# ina125.net
KiCad netlist of a schematic drawn in EAGLE
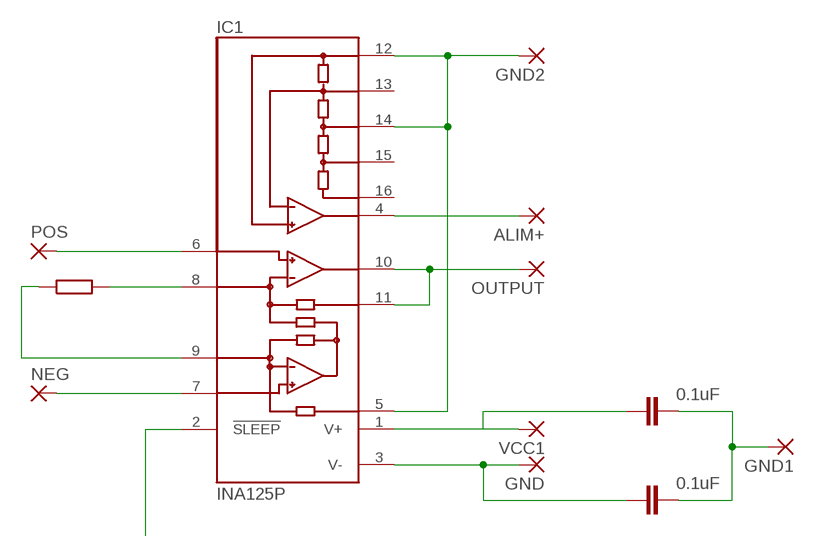
[diagram p0: schematic, sheet 1]

(export (version "E")
  (design (tool "Eeschema 10.0.6"))
  (components
    (comp (ref "ALIM+")
      (value "1,6/0,8")
      (footprint "eagle-import:1,6_0,8")
      (libsource (lib "eagle-import") (part "1,6/0,8"))
    )
    (comp (ref "C1")
      (value "0.1uF")
      (footprint "eagle-import:C2.5-3")
      (libsource (lib "eagle-import") (part "C2,5-3"))
    )
    (comp (ref "C2")
      (value "0.1uF")
      (footprint "eagle-import:C2.5-3")
      (libsource (lib "eagle-import") (part "C2,5-3"))
    )
    (comp (ref "GND")
      (value "1,6/0,8")
      (footprint "eagle-import:1,6_0,8")
      (libsource (lib "eagle-import") (part "1,6/0,8"))
    )
    (comp (ref "GND1")
      (value "1,6/0,8")
      (footprint "eagle-import:1,6_0,8")
      (libsource (lib "eagle-import") (part "1,6/0,8"))
    )
    (comp (ref "GND2")
      (value "1,6/0,8")
      (footprint "eagle-import:1,6_0,8")
      (libsource (lib "eagle-import") (part "1,6/0,8"))
    )
    (comp (ref "IC1")
      (value "INA125P")
      (footprint "eagle-import:DIL16")
      (libsource (lib "eagle-import") (part "INA125P"))
    )
    (comp (ref "NEG")
      (value "1,6/0,8")
      (footprint "eagle-import:1,6_0,8")
      (libsource (lib "eagle-import") (part "1,6/0,8"))
    )
    (comp (ref "OUTPUT")
      (value "1,6/0,8")
      (footprint "eagle-import:1,6_0,8")
      (libsource (lib "eagle-import") (part "1,6/0,8"))
    )
    (comp (ref "POS")
      (value "1,6/0,8")
      (footprint "eagle-import:1,6_0,8")
      (libsource (lib "eagle-import") (part "1,6/0,8"))
    )
    (comp (ref "VCC1")
      (value "1,6/0,8")
      (footprint "eagle-import:1,6_0,8")
      (libsource (lib "eagle-import") (part "1,6/0,8"))
    )
  )
  (nets
    (net (code "1") (name "Net-(ALIM+-P)") (class "Default")
      (node (ref "ALIM+") (pin "1") (pinfunction "P_1") (pintype "passive"))
      (node (ref "IC1") (pin "4") (pinfunction "REFOUT_4") (pintype "output"))
    )
    (net (code "2") (name "Net-(GND-P)") (class "Default")
      (node (ref "C2") (pin "1") (pinfunction "1_1") (pintype "passive"))
      (node (ref "GND") (pin "1") (pinfunction "P_1") (pintype "passive"))
      (node (ref "IC1") (pin "3") (pinfunction "V-_3") (pintype "power_in"))
    )
    (net (code "3") (name "Net-(GND1-P)") (class "Default")
      (node (ref "C1") (pin "2") (pinfunction "2_2") (pintype "passive"))
      (node (ref "C2") (pin "2") (pinfunction "2_2") (pintype "passive"))
      (node (ref "GND1") (pin "1") (pinfunction "P_1") (pintype "passive"))
    )
    (net (code "4") (name "Net-(GND2-P)") (class "Default")
      (node (ref "GND2") (pin "1") (pinfunction "P_1") (pintype "passive"))
      (node (ref "IC1") (pin "12") (pinfunction "REFCOM_12") (pintype "passive"))
      (node (ref "IC1") (pin "14") (pinfunction "REF2.5_14") (pintype "output"))
      (node (ref "IC1") (pin "5") (pinfunction "REF_5") (pintype "passive"))
    )
    (net (code "5") (name "Net-(IC1-+IN)") (class "Default")
      (node (ref "IC1") (pin "6") (pinfunction "+IN_6") (pintype "input"))
      (node (ref "POS") (pin "1") (pinfunction "P_1") (pintype "passive"))
    )
    (net (code "6") (name "Net-(IC1--IN)") (class "Default")
      (node (ref "IC1") (pin "7") (pinfunction "-IN_7") (pintype "input"))
      (node (ref "NEG") (pin "1") (pinfunction "P_1") (pintype "passive"))
    )
    (net (code "7") (name "Net-(IC1-OUT)") (class "Default")
      (node (ref "IC1") (pin "10") (pinfunction "OUT_10") (pintype "output"))
      (node (ref "IC1") (pin "11") (pinfunction "SENSE_11") (pintype "passive"))
      (node (ref "OUTPUT") (pin "1") (pinfunction "P_1") (pintype "passive"))
    )
    (net (code "8") (name "Net-(IC1-V+)") (class "Default")
      (node (ref "C1") (pin "1") (pinfunction "1_1") (pintype "passive"))
      (node (ref "IC1") (pin "1") (pinfunction "V+_1") (pintype "power_in"))
      (node (ref "VCC1") (pin "1") (pinfunction "P_1") (pintype "passive"))
    )
    (net (code "9") (name "unconnected-(IC1-REF5-Pad15)") (class "Default")
      (node (ref "IC1") (pin "15") (pinfunction "REF5_15") (pintype "output"))
    )
    (net (code "10") (name "unconnected-(IC1-REF10-Pad16)") (class "Default")
      (node (ref "IC1") (pin "16") (pinfunction "REF10_16") (pintype "output"))
    )
    (net (code "11") (name "unconnected-(IC1-REFBG-Pad13)") (class "Default")
      (node (ref "IC1") (pin "13") (pinfunction "REFBG_13") (pintype "output"))
    )
    (net (code "12") (name "unconnected-(IC1-RG-Pad8)") (class "Default")
      (node (ref "IC1") (pin "8") (pinfunction "RG_8") (pintype "passive"))
    )
    (net (code "13") (name "unconnected-(IC1-RG-Pad9)") (class "Default")
      (node (ref "IC1") (pin "9") (pinfunction "RG_9") (pintype "passive"))
    )
    (net (code "14") (name "unconnected-(IC1-~{SLEEP}-Pad2)") (class "Default")
      (node (ref "IC1") (pin "2") (pinfunction "~{SLEEP}_2") (pintype "input"))
    )
  )
)
